# shinobi_1v8-5v_3V3_jack.net
KiCad netlist of a schematic drawn in EAGLE
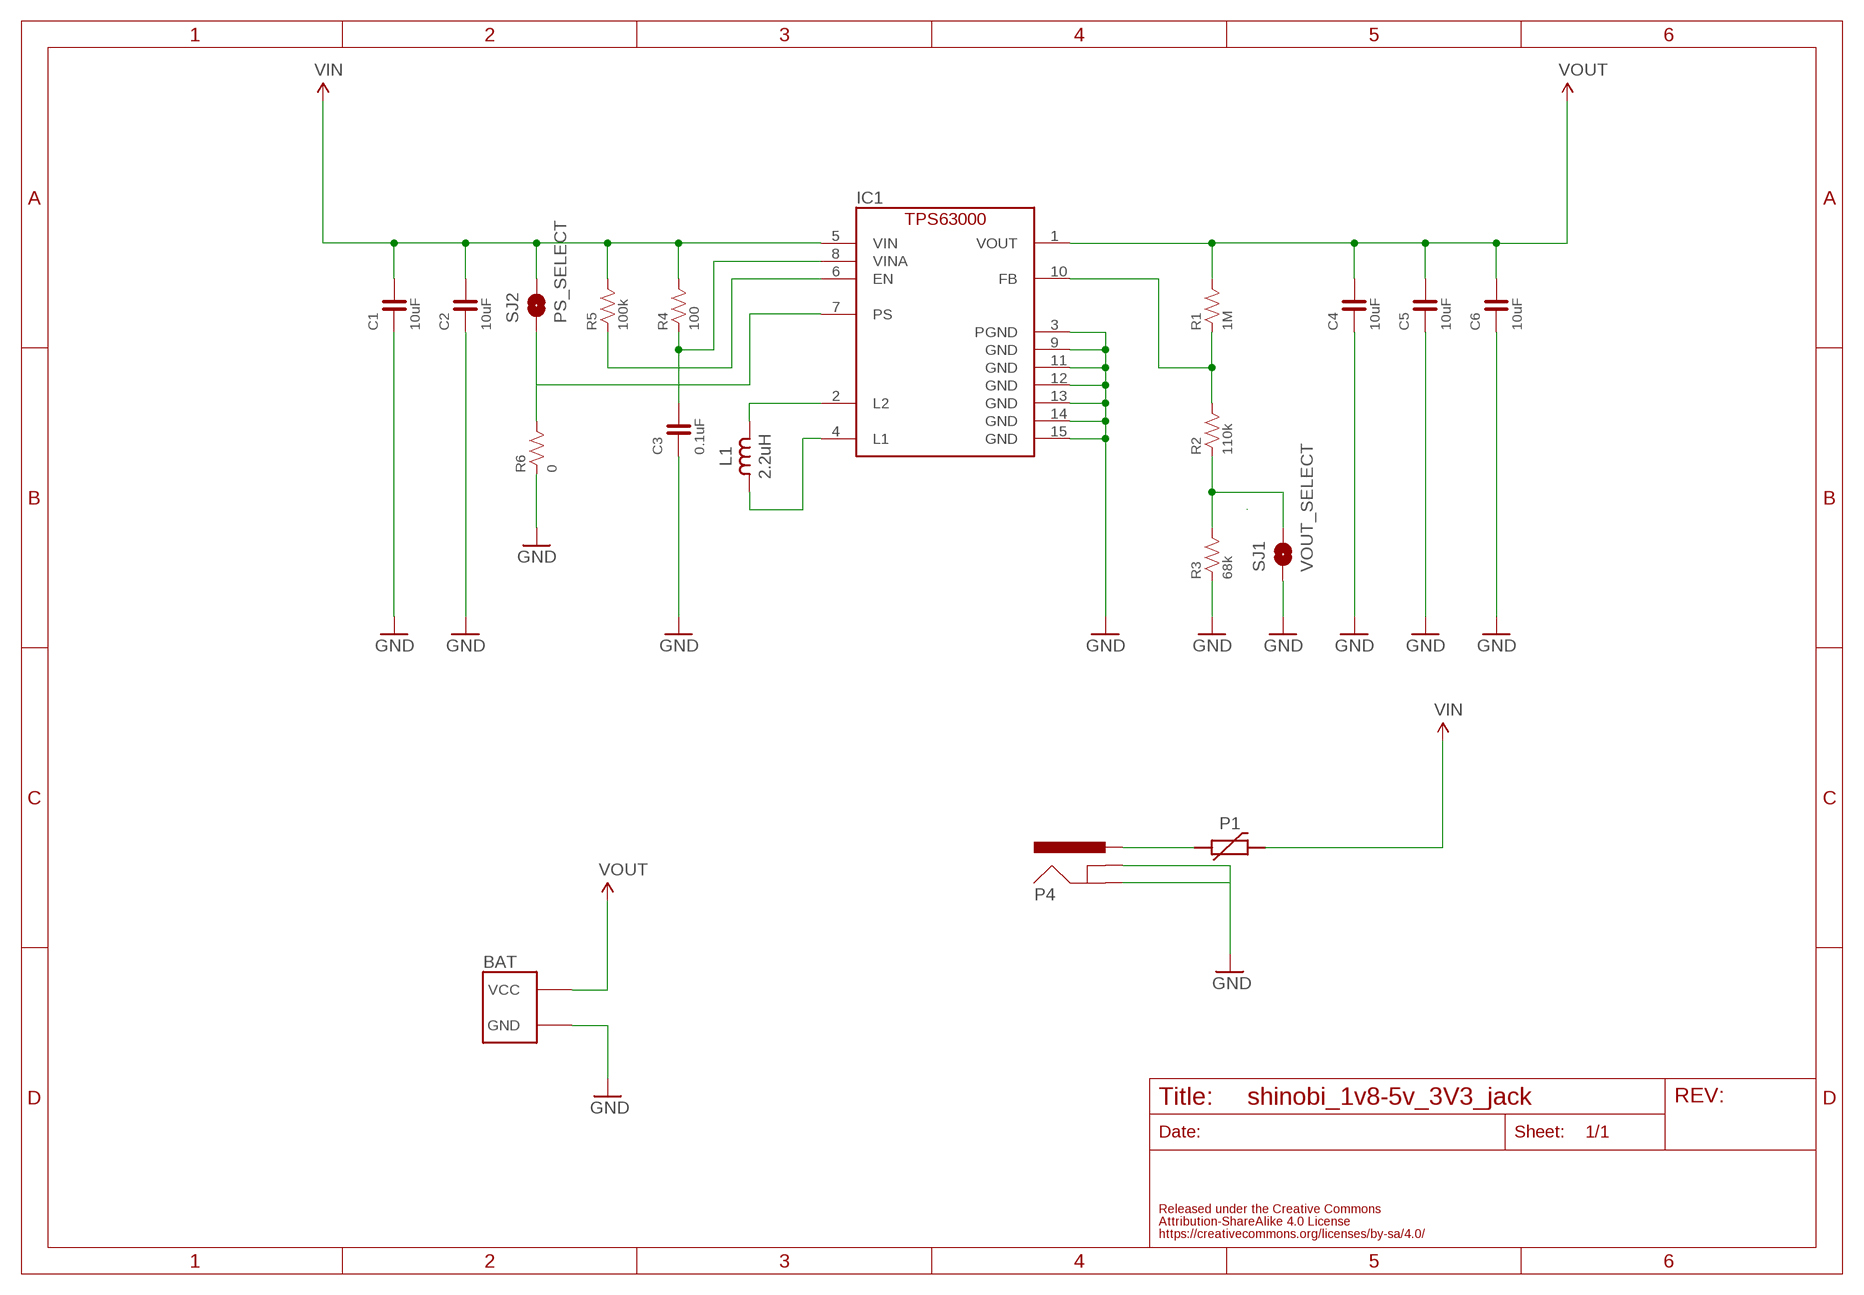
[diagram p0: schematic, sheet 1]

(export (version "E")
  (design (tool "Eeschema 10.0.6"))
  (components
    (comp (ref "BAT")
      (value "FABO_BRICK_2PIN_SIDE")
      (footprint "eagle-import:FABO_BRICK_2PIN_S02B−PASK-2_SILK")
      (libsource (lib "eagle-import") (part "FABO_BRICK_2PIN_SIDE"))
    )
    (comp (ref "C1")
      (value "10uF")
      (footprint "eagle-import:0603-NARROW")
      (libsource (lib "eagle-import") (part "CAPACITOR-0603_NARROW"))
    )
    (comp (ref "C2")
      (value "10uF")
      (footprint "eagle-import:0603-NARROW")
      (libsource (lib "eagle-import") (part "CAPACITOR-0603_NARROW"))
    )
    (comp (ref "C3")
      (value "0.1uF")
      (footprint "eagle-import:0603-NARROW")
      (libsource (lib "eagle-import") (part "CAPACITOR-0603_NARROW"))
    )
    (comp (ref "C4")
      (value "10uF")
      (footprint "eagle-import:0603-NARROW")
      (libsource (lib "eagle-import") (part "CAPACITOR-0603_NARROW"))
    )
    (comp (ref "C5")
      (value "10uF")
      (footprint "eagle-import:0603-NARROW")
      (libsource (lib "eagle-import") (part "CAPACITOR-0603_NARROW"))
    )
    (comp (ref "C6")
      (value "10uF")
      (footprint "eagle-import:0603-NARROW")
      (libsource (lib "eagle-import") (part "CAPACITOR-0603_NARROW"))
    )
    (comp (ref "IC1")
      (value "TPS63000DRC")
      (footprint "eagle-import:VSON-10")
      (libsource (lib "eagle-import") (part "TPS63000DRC"))
    )
    (comp (ref "L1")
      (value "2.2uH")
      (footprint "eagle-import:LQH3NPN")
      (libsource (lib "eagle-import") (part "INDUCTOR-LQH3NPN"))
    )
    (comp (ref "P1")
      (value "POLYSWITCH1210")
      (footprint "eagle-import:1210")
      (libsource (lib "eagle-import") (part "POLYSWITCH1210"))
    )
    (comp (ref "P4")
      (value "DC-JACKMA04339A0")
      (footprint "eagle-import:M04339A0")
      (libsource (lib "eagle-import") (part "DC-JACKMA04339A0"))
    )
    (comp (ref "R1")
      (value "1M")
      (footprint "eagle-import:0603-NARROW")
      (libsource (lib "eagle-import") (part "RESISTOR-0603-NARROW"))
    )
    (comp (ref "R2")
      (value "110k")
      (footprint "eagle-import:0603-NARROW")
      (libsource (lib "eagle-import") (part "RESISTOR-0603-NARROW"))
    )
    (comp (ref "R3")
      (value "68k")
      (footprint "eagle-import:0603-NARROW")
      (libsource (lib "eagle-import") (part "RESISTOR-0603-NARROW"))
    )
    (comp (ref "R4")
      (value "100")
      (footprint "eagle-import:0603-NARROW")
      (libsource (lib "eagle-import") (part "RESISTOR-0603-NARROW"))
    )
    (comp (ref "R5")
      (value "100k")
      (footprint "eagle-import:0603-NARROW")
      (libsource (lib "eagle-import") (part "RESISTOR-0603-NARROW"))
    )
    (comp (ref "R6")
      (value "0")
      (footprint "eagle-import:0603-NARROW")
      (libsource (lib "eagle-import") (part "RESISTOR-0603-NARROW"))
    )
    (comp (ref "SJ1")
      (value "VOUT_SELECT")
      (footprint "eagle-import:SMD-JUMPER-2-SHORT")
      (libsource (lib "eagle-import") (part "SMD-JUMPER-2-SHORT"))
    )
    (comp (ref "SJ2")
      (value "PS_SELECT")
      (footprint "eagle-import:SMD-JUMPER-2-SHORT")
      (libsource (lib "eagle-import") (part "SMD-JUMPER-2-SHORT"))
    )
  )
  (nets
    (net (code "1") (name "GND") (class "Default")
      (node (ref "BAT") (pin "GND") (pinfunction "GND_GND") (pintype "bidirectional"))
      (node (ref "C1") (pin "1") (pinfunction "1_1") (pintype "passive"))
      (node (ref "C2") (pin "1") (pinfunction "1_1") (pintype "passive"))
      (node (ref "C3") (pin "1") (pinfunction "1_1") (pintype "passive"))
      (node (ref "C4") (pin "1") (pinfunction "1_1") (pintype "passive"))
      (node (ref "C5") (pin "1") (pinfunction "1_1") (pintype "passive"))
      (node (ref "C6") (pin "1") (pinfunction "1_1") (pintype "passive"))
      (node (ref "IC1") (pin "11") (pinfunction "GND_11") (pintype "bidirectional"))
      (node (ref "IC1") (pin "12") (pinfunction "GND_12") (pintype "bidirectional"))
      (node (ref "IC1") (pin "13") (pinfunction "GND_13") (pintype "bidirectional"))
      (node (ref "IC1") (pin "14") (pinfunction "GND_14") (pintype "bidirectional"))
      (node (ref "IC1") (pin "15") (pinfunction "GND_15") (pintype "bidirectional"))
      (node (ref "IC1") (pin "3") (pinfunction "PGND_3") (pintype "bidirectional"))
      (node (ref "IC1") (pin "9") (pinfunction "GND_9") (pintype "bidirectional"))
      (node (ref "P4") (pin "GND@2") (pinfunction "GND_GND@2") (pintype "bidirectional"))
      (node (ref "P4") (pin "GND@3") (pinfunction "GNDBREAK_GND@3") (pintype "bidirectional"))
      (node (ref "R3") (pin "1") (pinfunction "1_1") (pintype "bidirectional"))
      (node (ref "R6") (pin "1") (pinfunction "1_1") (pintype "bidirectional"))
      (node (ref "SJ1") (pin "2") (pinfunction "2_2") (pintype "passive"))
    )
    (net (code "2") (name "Net-(IC1-EN)") (class "Default")
      (node (ref "IC1") (pin "6") (pinfunction "EN_6") (pintype "bidirectional"))
      (node (ref "R5") (pin "1") (pinfunction "1_1") (pintype "bidirectional"))
    )
    (net (code "3") (name "Net-(IC1-FB)") (class "Default")
      (node (ref "IC1") (pin "10") (pinfunction "FB_10") (pintype "bidirectional"))
      (node (ref "R1") (pin "1") (pinfunction "1_1") (pintype "bidirectional"))
      (node (ref "R2") (pin "2") (pinfunction "2_2") (pintype "bidirectional"))
    )
    (net (code "4") (name "Net-(IC1-L1)") (class "Default")
      (node (ref "IC1") (pin "4") (pinfunction "L1_4") (pintype "bidirectional"))
      (node (ref "L1") (pin "1") (pinfunction "1_1") (pintype "bidirectional"))
    )
    (net (code "5") (name "Net-(IC1-L2)") (class "Default")
      (node (ref "IC1") (pin "2") (pinfunction "L2_2") (pintype "bidirectional"))
      (node (ref "L1") (pin "2") (pinfunction "2_2") (pintype "bidirectional"))
    )
    (net (code "6") (name "Net-(IC1-PS)") (class "Default")
      (node (ref "IC1") (pin "7") (pinfunction "PS_7") (pintype "bidirectional"))
      (node (ref "R6") (pin "2") (pinfunction "2_2") (pintype "bidirectional"))
      (node (ref "SJ2") (pin "2") (pinfunction "2_2") (pintype "passive"))
    )
    (net (code "7") (name "Net-(IC1-VINA)") (class "Default")
      (node (ref "C3") (pin "2") (pinfunction "2_2") (pintype "passive"))
      (node (ref "IC1") (pin "8") (pinfunction "VINA_8") (pintype "bidirectional"))
      (node (ref "R4") (pin "1") (pinfunction "1_1") (pintype "bidirectional"))
    )
    (net (code "8") (name "Net-(P1-1)") (class "Default")
      (node (ref "P1") (pin "P$1") (pinfunction "1_P$1") (pintype "bidirectional"))
      (node (ref "P4") (pin "VCC") (pinfunction "PWR_VCC") (pintype "bidirectional"))
    )
    (net (code "9") (name "Net-(R2-Pad1)") (class "Default")
      (node (ref "R2") (pin "1") (pinfunction "1_1") (pintype "bidirectional"))
      (node (ref "R3") (pin "2") (pinfunction "2_2") (pintype "bidirectional"))
      (node (ref "SJ1") (pin "1") (pinfunction "1_1") (pintype "passive"))
    )
    (net (code "10") (name "VIN") (class "Default")
      (node (ref "C1") (pin "2") (pinfunction "2_2") (pintype "passive"))
      (node (ref "C2") (pin "2") (pinfunction "2_2") (pintype "passive"))
      (node (ref "IC1") (pin "5") (pinfunction "VIN_5") (pintype "bidirectional"))
      (node (ref "P1") (pin "P$2") (pinfunction "2_P$2") (pintype "bidirectional"))
      (node (ref "R4") (pin "2") (pinfunction "2_2") (pintype "bidirectional"))
      (node (ref "R5") (pin "2") (pinfunction "2_2") (pintype "bidirectional"))
      (node (ref "SJ2") (pin "1") (pinfunction "1_1") (pintype "passive"))
    )
    (net (code "11") (name "VOUT") (class "Default")
      (node (ref "BAT") (pin "VCC") (pinfunction "VCC_VCC") (pintype "bidirectional"))
      (node (ref "C4") (pin "2") (pinfunction "2_2") (pintype "passive"))
      (node (ref "C5") (pin "2") (pinfunction "2_2") (pintype "passive"))
      (node (ref "C6") (pin "2") (pinfunction "2_2") (pintype "passive"))
      (node (ref "IC1") (pin "1") (pinfunction "VOUT_1") (pintype "bidirectional"))
      (node (ref "R1") (pin "2") (pinfunction "2_2") (pintype "bidirectional"))
    )
  )
)
